# IO.net
KiCad netlist of a schematic drawn in Altium Designer
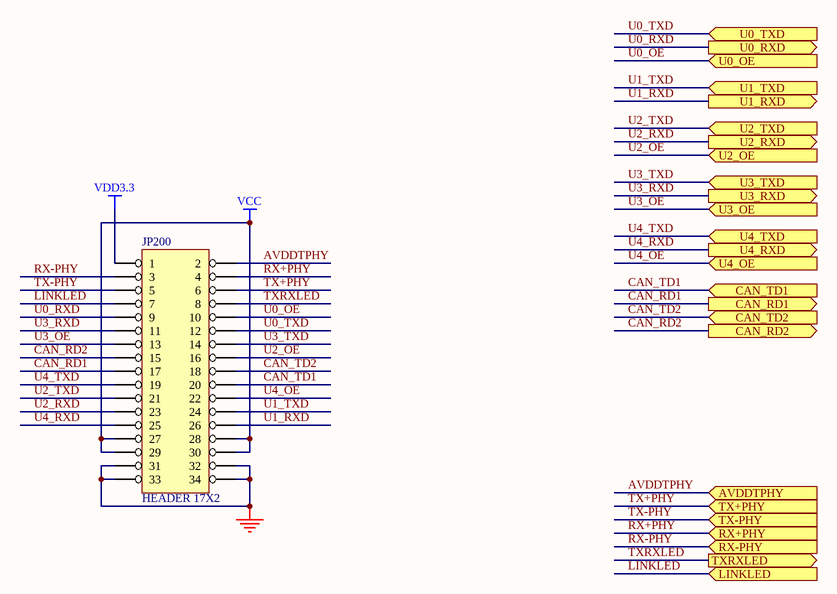
[diagram p0: IO.SchDoc]

(export (version "E")
  (design (tool "Eeschema 10.0.6"))
  (components
    (comp (ref "JP200") (value "HEADER 17X2") (footprint "IDC34") (libsource (lib "*") (part "HEADER 17X2")))
  )
  (nets
    (net (code "1") (name "/AVDDTPHY") (class "Default")
      (node (ref "JP200") (pin "2") (pinfunction "2_2") (pintype "passive"))
    )
    (net (code "2") (name "/CAN_RD1") (class "Default")
      (node (ref "JP200") (pin "17") (pinfunction "17_17") (pintype "passive"))
    )
    (net (code "3") (name "/CAN_RD2") (class "Default")
      (node (ref "JP200") (pin "15") (pinfunction "15_15") (pintype "passive"))
    )
    (net (code "4") (name "/CAN_TD1") (class "Default")
      (node (ref "JP200") (pin "20") (pinfunction "20_20") (pintype "passive"))
    )
    (net (code "5") (name "/CAN_TD2") (class "Default")
      (node (ref "JP200") (pin "18") (pinfunction "18_18") (pintype "passive"))
    )
    (net (code "6") (name "/LINKLED") (class "Default")
      (node (ref "JP200") (pin "7") (pinfunction "7_7") (pintype "passive"))
    )
    (net (code "7") (name "/RX+PHY") (class "Default")
      (node (ref "JP200") (pin "4") (pinfunction "4_4") (pintype "passive"))
    )
    (net (code "8") (name "/RX-PHY") (class "Default")
      (node (ref "JP200") (pin "3") (pinfunction "3_3") (pintype "passive"))
    )
    (net (code "9") (name "/TX+PHY") (class "Default")
      (node (ref "JP200") (pin "6") (pinfunction "6_6") (pintype "passive"))
    )
    (net (code "10") (name "/TX-PHY") (class "Default")
      (node (ref "JP200") (pin "5") (pinfunction "5_5") (pintype "passive"))
    )
    (net (code "11") (name "/TXRXLED") (class "Default")
      (node (ref "JP200") (pin "8") (pinfunction "8_8") (pintype "passive"))
    )
    (net (code "12") (name "/U0_OE") (class "Default")
      (node (ref "JP200") (pin "10") (pinfunction "10_10") (pintype "passive"))
    )
    (net (code "13") (name "/U0_RXD") (class "Default")
      (node (ref "JP200") (pin "9") (pinfunction "9_9") (pintype "passive"))
    )
    (net (code "14") (name "/U0_TXD") (class "Default")
      (node (ref "JP200") (pin "12") (pinfunction "12_12") (pintype "passive"))
    )
    (net (code "15") (name "/U1_RXD") (class "Default")
      (node (ref "JP200") (pin "26") (pinfunction "26_26") (pintype "passive"))
    )
    (net (code "16") (name "/U1_TXD") (class "Default")
      (node (ref "JP200") (pin "24") (pinfunction "24_24") (pintype "passive"))
    )
    (net (code "17") (name "/U2_OE") (class "Default")
      (node (ref "JP200") (pin "16") (pinfunction "16_16") (pintype "passive"))
    )
    (net (code "18") (name "/U2_RXD") (class "Default")
      (node (ref "JP200") (pin "23") (pinfunction "23_23") (pintype "passive"))
    )
    (net (code "19") (name "/U2_TXD") (class "Default")
      (node (ref "JP200") (pin "21") (pinfunction "21_21") (pintype "passive"))
    )
    (net (code "20") (name "/U3_OE") (class "Default")
      (node (ref "JP200") (pin "13") (pinfunction "13_13") (pintype "passive"))
    )
    (net (code "21") (name "/U3_RXD") (class "Default")
      (node (ref "JP200") (pin "11") (pinfunction "11_11") (pintype "passive"))
    )
    (net (code "22") (name "/U3_TXD") (class "Default")
      (node (ref "JP200") (pin "14") (pinfunction "14_14") (pintype "passive"))
    )
    (net (code "23") (name "/U4_OE") (class "Default")
      (node (ref "JP200") (pin "22") (pinfunction "22_22") (pintype "passive"))
    )
    (net (code "24") (name "/U4_RXD") (class "Default")
      (node (ref "JP200") (pin "25") (pinfunction "25_25") (pintype "passive"))
    )
    (net (code "25") (name "/U4_TXD") (class "Default")
      (node (ref "JP200") (pin "19") (pinfunction "19_19") (pintype "passive"))
    )
    (net (code "26") (name "GND") (class "Default")
      (node (ref "JP200") (pin "31") (pinfunction "31_31") (pintype "passive"))
      (node (ref "JP200") (pin "32") (pinfunction "32_32") (pintype "passive"))
      (node (ref "JP200") (pin "33") (pinfunction "33_33") (pintype "passive"))
      (node (ref "JP200") (pin "34") (pinfunction "34_34") (pintype "passive"))
    )
    (net (code "27") (name "VCC") (class "Default")
      (node (ref "JP200") (pin "27") (pinfunction "27_27") (pintype "passive"))
      (node (ref "JP200") (pin "28") (pinfunction "28_28") (pintype "passive"))
      (node (ref "JP200") (pin "29") (pinfunction "29_29") (pintype "passive"))
      (node (ref "JP200") (pin "30") (pinfunction "30_30") (pintype "passive"))
    )
    (net (code "28") (name "VDD3.3") (class "Default")
      (node (ref "JP200") (pin "1") (pinfunction "1_1") (pintype "passive"))
    )
  )
)
